# Divider.net
KiCad netlist of a schematic drawn in EAGLE
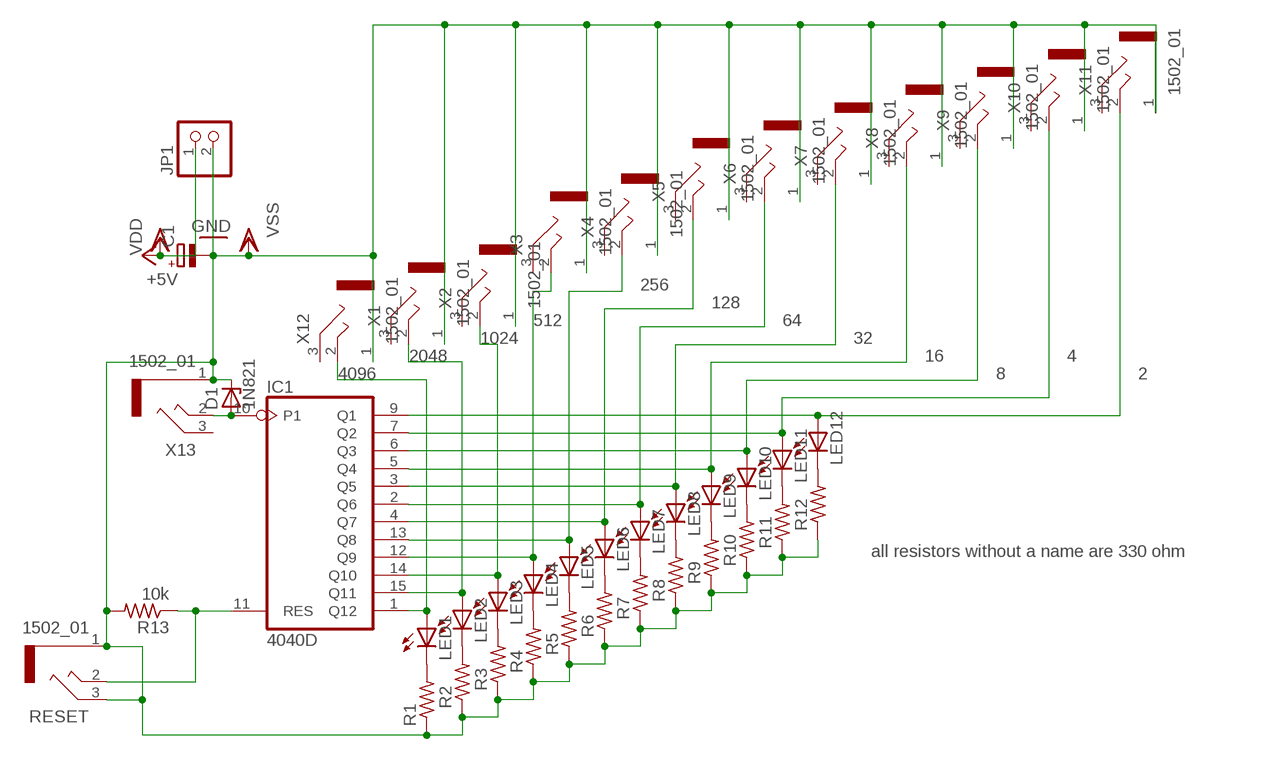
[diagram p0: schematic, sheet 1]

(export (version "E")
  (design (tool "Eeschema 10.0.6"))
  (components
    (comp (ref "C1")
      (value "CPOL-EUE2,5-6E")
      (footprint "eagle-import:E2,5-6E")
      (libsource (lib "eagle-import") (part "CPOL-EUE2,5-6E"))
    )
    (comp (ref "D1")
      (value "1N821")
      (footprint "eagle-import:DO35Z10")
      (libsource (lib "eagle-import") (part "1N821"))
    )
    (comp (ref "IC1")
      (value "4040D")
      (footprint "eagle-import:SO16")
      (libsource (lib "eagle-import") (part "4040D"))
    )
    (comp (ref "JP1")
      (value "PINHD-1X2")
      (footprint "eagle-import:1X02")
      (libsource (lib "eagle-import") (part "PINHD-1X2"))
    )
    (comp (ref "LED1")
      (value "LED5MM")
      (footprint "eagle-import:LED5MM")
      (libsource (lib "eagle-import") (part "LED5MM"))
    )
    (comp (ref "LED2")
      (value "LED5MM")
      (footprint "eagle-import:LED5MM")
      (libsource (lib "eagle-import") (part "LED5MM"))
    )
    (comp (ref "LED3")
      (value "LED5MM")
      (footprint "eagle-import:LED5MM")
      (libsource (lib "eagle-import") (part "LED5MM"))
    )
    (comp (ref "LED4")
      (value "LED5MM")
      (footprint "eagle-import:LED5MM")
      (libsource (lib "eagle-import") (part "LED5MM"))
    )
    (comp (ref "LED5")
      (value "LED5MM")
      (footprint "eagle-import:LED5MM")
      (libsource (lib "eagle-import") (part "LED5MM"))
    )
    (comp (ref "LED6")
      (value "LED5MM")
      (footprint "eagle-import:LED5MM")
      (libsource (lib "eagle-import") (part "LED5MM"))
    )
    (comp (ref "LED7")
      (value "LED5MM")
      (footprint "eagle-import:LED5MM")
      (libsource (lib "eagle-import") (part "LED5MM"))
    )
    (comp (ref "LED8")
      (value "LED5MM")
      (footprint "eagle-import:LED5MM")
      (libsource (lib "eagle-import") (part "LED5MM"))
    )
    (comp (ref "LED9")
      (value "LED5MM")
      (footprint "eagle-import:LED5MM")
      (libsource (lib "eagle-import") (part "LED5MM"))
    )
    (comp (ref "LED10")
      (value "LED5MM")
      (footprint "eagle-import:LED5MM")
      (libsource (lib "eagle-import") (part "LED5MM"))
    )
    (comp (ref "LED11")
      (value "LED5MM")
      (footprint "eagle-import:LED5MM")
      (libsource (lib "eagle-import") (part "LED5MM"))
    )
    (comp (ref "LED12")
      (value "LED5MM")
      (footprint "eagle-import:LED5MM")
      (libsource (lib "eagle-import") (part "LED5MM"))
    )
    (comp (ref "R1")
      (value "R-US_0204/7")
      (footprint "eagle-import:0204_7")
      (libsource (lib "eagle-import") (part "R-US_0204/7"))
    )
    (comp (ref "R2")
      (value "R-US_0204/7")
      (footprint "eagle-import:0204_7")
      (libsource (lib "eagle-import") (part "R-US_0204/7"))
    )
    (comp (ref "R3")
      (value "R-US_0204/7")
      (footprint "eagle-import:0204_7")
      (libsource (lib "eagle-import") (part "R-US_0204/7"))
    )
    (comp (ref "R4")
      (value "R-US_0204/7")
      (footprint "eagle-import:0204_7")
      (libsource (lib "eagle-import") (part "R-US_0204/7"))
    )
    (comp (ref "R5")
      (value "R-US_0204/7")
      (footprint "eagle-import:0204_7")
      (libsource (lib "eagle-import") (part "R-US_0204/7"))
    )
    (comp (ref "R6")
      (value "R-US_0204/7")
      (footprint "eagle-import:0204_7")
      (libsource (lib "eagle-import") (part "R-US_0204/7"))
    )
    (comp (ref "R7")
      (value "R-US_0204/7")
      (footprint "eagle-import:0204_7")
      (libsource (lib "eagle-import") (part "R-US_0204/7"))
    )
    (comp (ref "R8")
      (value "R-US_0204/7")
      (footprint "eagle-import:0204_7")
      (libsource (lib "eagle-import") (part "R-US_0204/7"))
    )
    (comp (ref "R9")
      (value "R-US_0204/7")
      (footprint "eagle-import:0204_7")
      (libsource (lib "eagle-import") (part "R-US_0204/7"))
    )
    (comp (ref "R10")
      (value "R-US_0204/7")
      (footprint "eagle-import:0204_7")
      (libsource (lib "eagle-import") (part "R-US_0204/7"))
    )
    (comp (ref "R11")
      (value "R-US_0204/7")
      (footprint "eagle-import:0204_7")
      (libsource (lib "eagle-import") (part "R-US_0204/7"))
    )
    (comp (ref "R12")
      (value "R-US_0204/7")
      (footprint "eagle-import:0204_7")
      (libsource (lib "eagle-import") (part "R-US_0204/7"))
    )
    (comp (ref "R13")
      (value "10k")
      (footprint "eagle-import:0204_7")
      (libsource (lib "eagle-import") (part "R-US_0204/7"))
    )
    (comp (ref "RESET")
      (value "1502_01")
      (footprint "eagle-import:1502_01")
      (libsource (lib "eagle-import") (part "1502_01"))
    )
    (comp (ref "X1")
      (value "1502_01")
      (footprint "eagle-import:1502_01")
      (libsource (lib "eagle-import") (part "1502_01"))
    )
    (comp (ref "X2")
      (value "1502_01")
      (footprint "eagle-import:1502_01")
      (libsource (lib "eagle-import") (part "1502_01"))
    )
    (comp (ref "X3")
      (value "1502_01")
      (footprint "eagle-import:1502_01")
      (libsource (lib "eagle-import") (part "1502_01"))
    )
    (comp (ref "X4")
      (value "1502_01")
      (footprint "eagle-import:1502_01")
      (libsource (lib "eagle-import") (part "1502_01"))
    )
    (comp (ref "X5")
      (value "1502_01")
      (footprint "eagle-import:1502_01")
      (libsource (lib "eagle-import") (part "1502_01"))
    )
    (comp (ref "X6")
      (value "1502_01")
      (footprint "eagle-import:1502_01")
      (libsource (lib "eagle-import") (part "1502_01"))
    )
    (comp (ref "X7")
      (value "1502_01")
      (footprint "eagle-import:1502_01")
      (libsource (lib "eagle-import") (part "1502_01"))
    )
    (comp (ref "X8")
      (value "1502_01")
      (footprint "eagle-import:1502_01")
      (libsource (lib "eagle-import") (part "1502_01"))
    )
    (comp (ref "X9")
      (value "1502_01")
      (footprint "eagle-import:1502_01")
      (libsource (lib "eagle-import") (part "1502_01"))
    )
    (comp (ref "X10")
      (value "1502_01")
      (footprint "eagle-import:1502_01")
      (libsource (lib "eagle-import") (part "1502_01"))
    )
    (comp (ref "X11")
      (value "1502_01")
      (footprint "eagle-import:1502_01")
      (libsource (lib "eagle-import") (part "1502_01"))
    )
    (comp (ref "X12")
      (value "1502_01")
      (footprint "eagle-import:1502_01")
      (libsource (lib "eagle-import") (part "1502_01"))
    )
    (comp (ref "X13")
      (value "1502_01")
      (footprint "eagle-import:1502_01")
      (libsource (lib "eagle-import") (part "1502_01"))
    )
  )
  (nets
    (net (code "1") (name "+5V") (class "Default")
      (node (ref "C1") (pin "+") (pinfunction "+_+") (pintype "passive"))
      (node (ref "JP1") (pin "1") (pinfunction "1_1") (pintype "passive"))
    )
    (net (code "2") (name "/2") (class "Default")
      (node (ref "IC1") (pin "9") (pinfunction "Q1_9") (pintype "output"))
      (node (ref "LED12") (pin "A") (pinfunction "A_A") (pintype "passive"))
      (node (ref "X11") (pin "2") (pinfunction "3_2") (pintype "passive"))
    )
    (net (code "3") (name "/4") (class "Default")
      (node (ref "IC1") (pin "7") (pinfunction "Q2_7") (pintype "output"))
      (node (ref "LED11") (pin "A") (pinfunction "A_A") (pintype "passive"))
      (node (ref "X10") (pin "2") (pinfunction "3_2") (pintype "passive"))
    )
    (net (code "4") (name "/8") (class "Default")
      (node (ref "IC1") (pin "6") (pinfunction "Q3_6") (pintype "output"))
      (node (ref "LED10") (pin "A") (pinfunction "A_A") (pintype "passive"))
      (node (ref "X9") (pin "2") (pinfunction "3_2") (pintype "passive"))
    )
    (net (code "5") (name "/16") (class "Default")
      (node (ref "IC1") (pin "5") (pinfunction "Q4_5") (pintype "output"))
      (node (ref "LED9") (pin "A") (pinfunction "A_A") (pintype "passive"))
      (node (ref "X8") (pin "2") (pinfunction "3_2") (pintype "passive"))
    )
    (net (code "6") (name "/32") (class "Default")
      (node (ref "IC1") (pin "3") (pinfunction "Q5_3") (pintype "output"))
      (node (ref "LED8") (pin "A") (pinfunction "A_A") (pintype "passive"))
      (node (ref "X7") (pin "2") (pinfunction "3_2") (pintype "passive"))
    )
    (net (code "7") (name "/64") (class "Default")
      (node (ref "IC1") (pin "2") (pinfunction "Q6_2") (pintype "output"))
      (node (ref "LED7") (pin "A") (pinfunction "A_A") (pintype "passive"))
      (node (ref "X6") (pin "2") (pinfunction "3_2") (pintype "passive"))
    )
    (net (code "8") (name "/128") (class "Default")
      (node (ref "IC1") (pin "4") (pinfunction "Q7_4") (pintype "output"))
      (node (ref "LED6") (pin "A") (pinfunction "A_A") (pintype "passive"))
      (node (ref "X5") (pin "2") (pinfunction "3_2") (pintype "passive"))
    )
    (net (code "9") (name "/256") (class "Default")
      (node (ref "IC1") (pin "13") (pinfunction "Q8_13") (pintype "output"))
      (node (ref "LED5") (pin "A") (pinfunction "A_A") (pintype "passive"))
      (node (ref "X4") (pin "2") (pinfunction "3_2") (pintype "passive"))
    )
    (net (code "10") (name "/512") (class "Default")
      (node (ref "IC1") (pin "12") (pinfunction "Q9_12") (pintype "output"))
      (node (ref "LED4") (pin "A") (pinfunction "A_A") (pintype "passive"))
      (node (ref "X3") (pin "2") (pinfunction "3_2") (pintype "passive"))
    )
    (net (code "11") (name "/1024") (class "Default")
      (node (ref "IC1") (pin "14") (pinfunction "Q10_14") (pintype "output"))
      (node (ref "LED3") (pin "A") (pinfunction "A_A") (pintype "passive"))
      (node (ref "X2") (pin "2") (pinfunction "3_2") (pintype "passive"))
    )
    (net (code "12") (name "/2048") (class "Default")
      (node (ref "IC1") (pin "15") (pinfunction "Q11_15") (pintype "output"))
      (node (ref "LED2") (pin "A") (pinfunction "A_A") (pintype "passive"))
      (node (ref "X1") (pin "2") (pinfunction "3_2") (pintype "passive"))
    )
    (net (code "13") (name "/4096") (class "Default")
      (node (ref "IC1") (pin "1") (pinfunction "Q12_1") (pintype "output"))
      (node (ref "LED1") (pin "A") (pinfunction "A_A") (pintype "passive"))
      (node (ref "X12") (pin "2") (pinfunction "3_2") (pintype "passive"))
    )
    (net (code "14") (name "GND") (class "Default")
      (node (ref "C1") (pin "-") (pinfunction "-_-") (pintype "passive"))
      (node (ref "D1") (pin "C") (pinfunction "C_C") (pintype "passive"))
      (node (ref "JP1") (pin "2") (pinfunction "2_2") (pintype "passive"))
      (node (ref "R1") (pin "1") (pinfunction "1_1") (pintype "passive"))
      (node (ref "R10") (pin "1") (pinfunction "1_1") (pintype "passive"))
      (node (ref "R11") (pin "1") (pinfunction "1_1") (pintype "passive"))
      (node (ref "R12") (pin "1") (pinfunction "1_1") (pintype "passive"))
      (node (ref "R13") (pin "2") (pinfunction "2_2") (pintype "passive"))
      (node (ref "R2") (pin "1") (pinfunction "1_1") (pintype "passive"))
      (node (ref "R3") (pin "1") (pinfunction "1_1") (pintype "passive"))
      (node (ref "R4") (pin "1") (pinfunction "1_1") (pintype "passive"))
      (node (ref "R5") (pin "1") (pinfunction "1_1") (pintype "passive"))
      (node (ref "R6") (pin "1") (pinfunction "1_1") (pintype "passive"))
      (node (ref "R7") (pin "1") (pinfunction "1_1") (pintype "passive"))
      (node (ref "R8") (pin "1") (pinfunction "1_1") (pintype "passive"))
      (node (ref "R9") (pin "1") (pinfunction "1_1") (pintype "passive"))
      (node (ref "RESET") (pin "1") (pinfunction "1_1") (pintype "passive"))
      (node (ref "RESET") (pin "3") (pinfunction "2_3") (pintype "passive"))
      (node (ref "X1") (pin "1") (pinfunction "1_1") (pintype "passive"))
      (node (ref "X10") (pin "1") (pinfunction "1_1") (pintype "passive"))
      (node (ref "X11") (pin "1") (pinfunction "1_1") (pintype "passive"))
      (node (ref "X12") (pin "1") (pinfunction "1_1") (pintype "passive"))
      (node (ref "X13") (pin "1") (pinfunction "1_1") (pintype "passive"))
      (node (ref "X2") (pin "1") (pinfunction "1_1") (pintype "passive"))
      (node (ref "X3") (pin "1") (pinfunction "1_1") (pintype "passive"))
      (node (ref "X4") (pin "1") (pinfunction "1_1") (pintype "passive"))
      (node (ref "X5") (pin "1") (pinfunction "1_1") (pintype "passive"))
      (node (ref "X6") (pin "1") (pinfunction "1_1") (pintype "passive"))
      (node (ref "X7") (pin "1") (pinfunction "1_1") (pintype "passive"))
      (node (ref "X8") (pin "1") (pinfunction "1_1") (pintype "passive"))
      (node (ref "X9") (pin "1") (pinfunction "1_1") (pintype "passive"))
    )
    (net (code "15") (name "Net-(IC1A-P1)") (class "Default")
      (node (ref "D1") (pin "A") (pinfunction "A_A") (pintype "passive"))
      (node (ref "IC1") (pin "10") (pinfunction "P1_10") (pintype "input"))
      (node (ref "X13") (pin "2") (pinfunction "3_2") (pintype "passive"))
    )
    (net (code "16") (name "Net-(IC1A-RES)") (class "Default")
      (node (ref "IC1") (pin "11") (pinfunction "RES_11") (pintype "input"))
      (node (ref "R13") (pin "1") (pinfunction "1_1") (pintype "passive"))
      (node (ref "RESET") (pin "2") (pinfunction "3_2") (pintype "passive"))
    )
    (net (code "17") (name "Net-(LED1-C)") (class "Default")
      (node (ref "LED1") (pin "K") (pinfunction "C_K") (pintype "passive"))
      (node (ref "R1") (pin "2") (pinfunction "2_2") (pintype "passive"))
    )
    (net (code "18") (name "Net-(LED2-C)") (class "Default")
      (node (ref "LED2") (pin "K") (pinfunction "C_K") (pintype "passive"))
      (node (ref "R2") (pin "2") (pinfunction "2_2") (pintype "passive"))
    )
    (net (code "19") (name "Net-(LED3-C)") (class "Default")
      (node (ref "LED3") (pin "K") (pinfunction "C_K") (pintype "passive"))
      (node (ref "R3") (pin "2") (pinfunction "2_2") (pintype "passive"))
    )
    (net (code "20") (name "Net-(LED4-C)") (class "Default")
      (node (ref "LED4") (pin "K") (pinfunction "C_K") (pintype "passive"))
      (node (ref "R4") (pin "2") (pinfunction "2_2") (pintype "passive"))
    )
    (net (code "21") (name "Net-(LED5-C)") (class "Default")
      (node (ref "LED5") (pin "K") (pinfunction "C_K") (pintype "passive"))
      (node (ref "R5") (pin "2") (pinfunction "2_2") (pintype "passive"))
    )
    (net (code "22") (name "Net-(LED6-C)") (class "Default")
      (node (ref "LED6") (pin "K") (pinfunction "C_K") (pintype "passive"))
      (node (ref "R6") (pin "2") (pinfunction "2_2") (pintype "passive"))
    )
    (net (code "23") (name "Net-(LED7-C)") (class "Default")
      (node (ref "LED7") (pin "K") (pinfunction "C_K") (pintype "passive"))
      (node (ref "R7") (pin "2") (pinfunction "2_2") (pintype "passive"))
    )
    (net (code "24") (name "Net-(LED8-C)") (class "Default")
      (node (ref "LED8") (pin "K") (pinfunction "C_K") (pintype "passive"))
      (node (ref "R8") (pin "2") (pinfunction "2_2") (pintype "passive"))
    )
    (net (code "25") (name "Net-(LED9-C)") (class "Default")
      (node (ref "LED9") (pin "K") (pinfunction "C_K") (pintype "passive"))
      (node (ref "R9") (pin "2") (pinfunction "2_2") (pintype "passive"))
    )
    (net (code "26") (name "Net-(LED10-C)") (class "Default")
      (node (ref "LED10") (pin "K") (pinfunction "C_K") (pintype "passive"))
      (node (ref "R10") (pin "2") (pinfunction "2_2") (pintype "passive"))
    )
    (net (code "27") (name "Net-(LED11-C)") (class "Default")
      (node (ref "LED11") (pin "K") (pinfunction "C_K") (pintype "passive"))
      (node (ref "R11") (pin "2") (pinfunction "2_2") (pintype "passive"))
    )
    (net (code "28") (name "Net-(LED12-C)") (class "Default")
      (node (ref "LED12") (pin "K") (pinfunction "C_K") (pintype "passive"))
      (node (ref "R12") (pin "2") (pinfunction "2_2") (pintype "passive"))
    )
    (net (code "29") (name "unconnected-(X1-2-Pad3)") (class "Default")
      (node (ref "X1") (pin "3") (pinfunction "2_3") (pintype "passive"))
    )
    (net (code "30") (name "unconnected-(X2-2-Pad3)") (class "Default")
      (node (ref "X2") (pin "3") (pinfunction "2_3") (pintype "passive"))
    )
    (net (code "31") (name "unconnected-(X3-2-Pad3)") (class "Default")
      (node (ref "X3") (pin "3") (pinfunction "2_3") (pintype "passive"))
    )
    (net (code "32") (name "unconnected-(X4-2-Pad3)") (class "Default")
      (node (ref "X4") (pin "3") (pinfunction "2_3") (pintype "passive"))
    )
    (net (code "33") (name "unconnected-(X5-2-Pad3)") (class "Default")
      (node (ref "X5") (pin "3") (pinfunction "2_3") (pintype "passive"))
    )
    (net (code "34") (name "unconnected-(X6-2-Pad3)") (class "Default")
      (node (ref "X6") (pin "3") (pinfunction "2_3") (pintype "passive"))
    )
    (net (code "35") (name "unconnected-(X7-2-Pad3)") (class "Default")
      (node (ref "X7") (pin "3") (pinfunction "2_3") (pintype "passive"))
    )
    (net (code "36") (name "unconnected-(X8-2-Pad3)") (class "Default")
      (node (ref "X8") (pin "3") (pinfunction "2_3") (pintype "passive"))
    )
    (net (code "37") (name "unconnected-(X9-2-Pad3)") (class "Default")
      (node (ref "X9") (pin "3") (pinfunction "2_3") (pintype "passive"))
    )
    (net (code "38") (name "unconnected-(X10-2-Pad3)") (class "Default")
      (node (ref "X10") (pin "3") (pinfunction "2_3") (pintype "passive"))
    )
    (net (code "39") (name "unconnected-(X11-2-Pad3)") (class "Default")
      (node (ref "X11") (pin "3") (pinfunction "2_3") (pintype "passive"))
    )
    (net (code "40") (name "unconnected-(X12-2-Pad3)") (class "Default")
      (node (ref "X12") (pin "3") (pinfunction "2_3") (pintype "passive"))
    )
    (net (code "41") (name "unconnected-(X13-2-Pad3)") (class "Default")
      (node (ref "X13") (pin "3") (pinfunction "2_3") (pintype "passive"))
    )
  )
)
